# Laser_Centraal.net
KiCad netlist of a schematic drawn in EAGLE
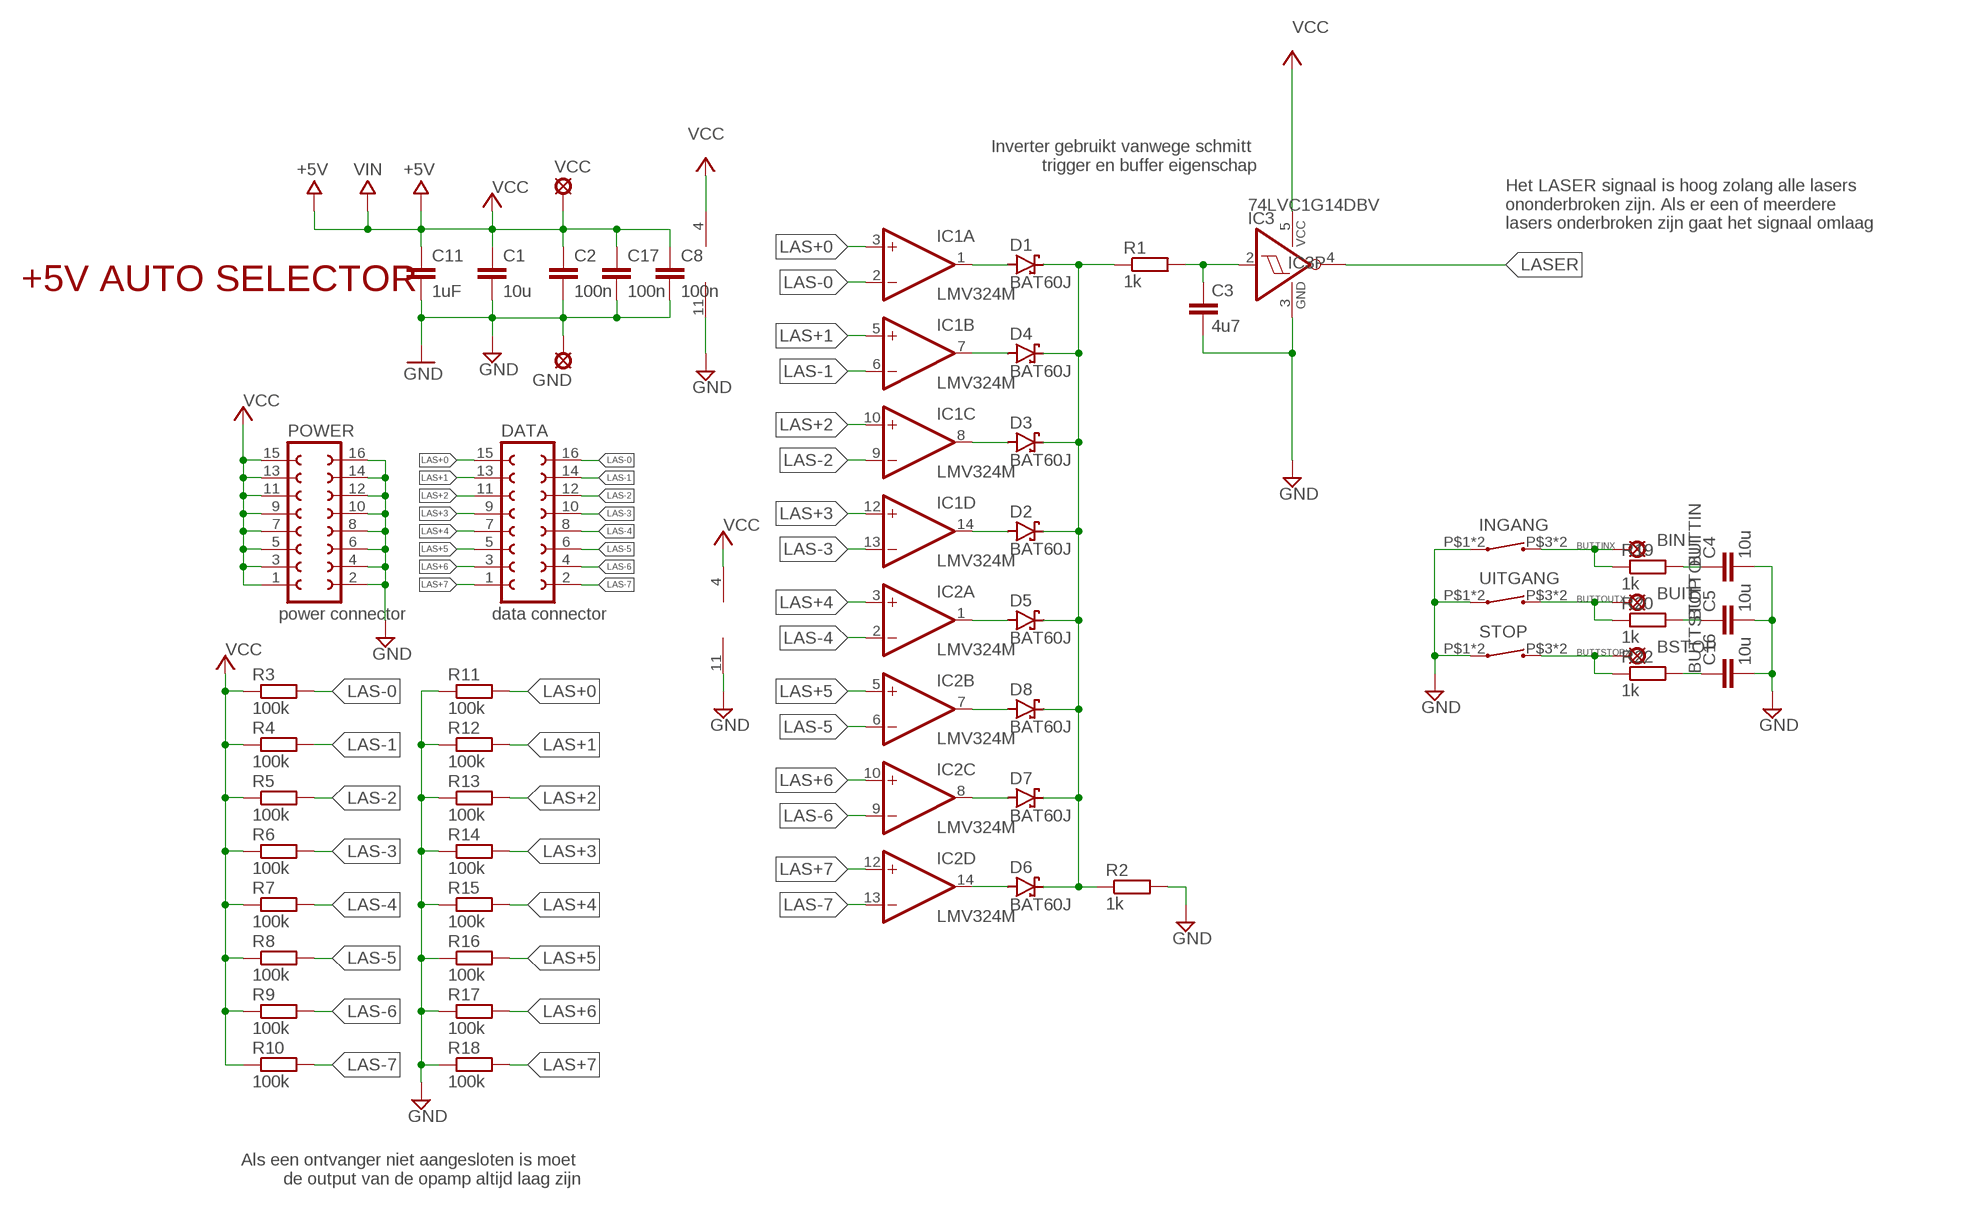
[diagram p0: schematic, sheet 1, part 1 of 2]
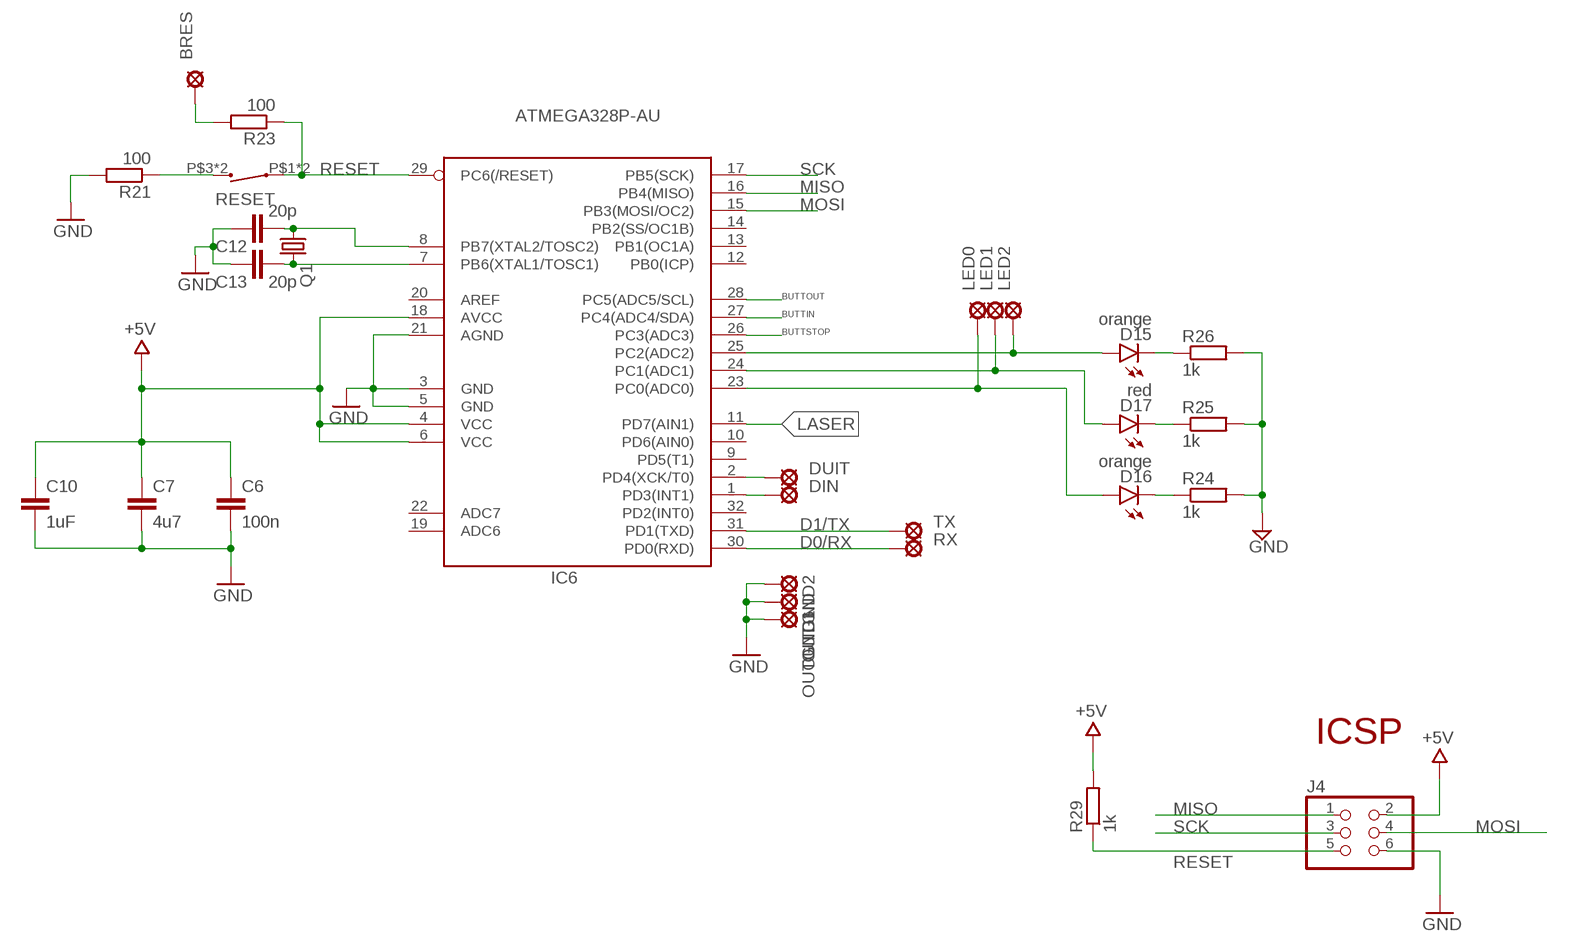
[diagram p1: schematic, sheet 1, part 2 of 2]

(export (version "E")
  (design (tool "Eeschema 10.0.6"))
  (components
    (comp (ref "BIN")
      (value "LSP10")
      (footprint "eagle-import:LSP10")
      (libsource (lib "eagle-import") (part "LSP10"))
    )
    (comp (ref "BRES")
      (value "LSP10")
      (footprint "eagle-import:LSP10")
      (libsource (lib "eagle-import") (part "LSP10"))
    )
    (comp (ref "BSTOP")
      (value "LSP10")
      (footprint "eagle-import:LSP10")
      (libsource (lib "eagle-import") (part "LSP10"))
    )
    (comp (ref "BUIT")
      (value "LSP10")
      (footprint "eagle-import:LSP10")
      (libsource (lib "eagle-import") (part "LSP10"))
    )
    (comp (ref "C1")
      (value "10u")
      (footprint "eagle-import:C0805")
      (libsource (lib "eagle-import") (part "C-EUC0805"))
    )
    (comp (ref "C2")
      (value "100n")
      (footprint "eagle-import:C0805")
      (libsource (lib "eagle-import") (part "C-EUC0805"))
    )
    (comp (ref "C3")
      (value "4u7")
      (footprint "eagle-import:C0805")
      (libsource (lib "eagle-import") (part "resistor_348_C-EUC0805"))
    )
    (comp (ref "C4")
      (value "10u")
      (footprint "eagle-import:C0805")
      (libsource (lib "eagle-import") (part "resistor_348_C-EUC0805"))
    )
    (comp (ref "C5")
      (value "10u")
      (footprint "eagle-import:C0805")
      (libsource (lib "eagle-import") (part "resistor_348_C-EUC0805"))
    )
    (comp (ref "C6")
      (value "100n")
      (footprint "eagle-import:C0805")
      (libsource (lib "eagle-import") (part "C-EUC0805"))
    )
    (comp (ref "C7")
      (value "4u7")
      (footprint "eagle-import:C0805")
      (libsource (lib "eagle-import") (part "C-EUC0805"))
    )
    (comp (ref "C8")
      (value "100n")
      (footprint "eagle-import:C0805")
      (libsource (lib "eagle-import") (part "C-EUC0805"))
    )
    (comp (ref "C10")
      (value "1uF")
      (footprint "eagle-import:C0805")
      (libsource (lib "eagle-import") (part "C-EUC0805"))
    )
    (comp (ref "C11")
      (value "1uF")
      (footprint "eagle-import:C0805")
      (libsource (lib "eagle-import") (part "C-EUC0805"))
    )
    (comp (ref "C12")
      (value "20p")
      (footprint "eagle-import:C0805")
      (libsource (lib "eagle-import") (part "C-EUC0805"))
    )
    (comp (ref "C13")
      (value "20p")
      (footprint "eagle-import:C0805")
      (libsource (lib "eagle-import") (part "C-EUC0805"))
    )
    (comp (ref "C16")
      (value "10u")
      (footprint "eagle-import:C0805")
      (libsource (lib "eagle-import") (part "resistor_348_C-EUC0805"))
    )
    (comp (ref "C17")
      (value "100n")
      (footprint "eagle-import:C0805")
      (libsource (lib "eagle-import") (part "C-EUC0805"))
    )
    (comp (ref "D1")
      (value "BAT60J")
      (footprint "eagle-import:SOD323_ST")
      (libsource (lib "eagle-import") (part "BAT60J"))
    )
    (comp (ref "D2")
      (value "BAT60J")
      (footprint "eagle-import:SOD323_ST")
      (libsource (lib "eagle-import") (part "BAT60J"))
    )
    (comp (ref "D3")
      (value "BAT60J")
      (footprint "eagle-import:SOD323_ST")
      (libsource (lib "eagle-import") (part "BAT60J"))
    )
    (comp (ref "D4")
      (value "BAT60J")
      (footprint "eagle-import:SOD323_ST")
      (libsource (lib "eagle-import") (part "BAT60J"))
    )
    (comp (ref "D5")
      (value "BAT60J")
      (footprint "eagle-import:SOD323_ST")
      (libsource (lib "eagle-import") (part "BAT60J"))
    )
    (comp (ref "D6")
      (value "BAT60J")
      (footprint "eagle-import:SOD323_ST")
      (libsource (lib "eagle-import") (part "BAT60J"))
    )
    (comp (ref "D7")
      (value "BAT60J")
      (footprint "eagle-import:SOD323_ST")
      (libsource (lib "eagle-import") (part "BAT60J"))
    )
    (comp (ref "D8")
      (value "BAT60J")
      (footprint "eagle-import:SOD323_ST")
      (libsource (lib "eagle-import") (part "BAT60J"))
    )
    (comp (ref "D15")
      (value "orange")
      (footprint "eagle-import:CHIP-LED0805")
      (libsource (lib "eagle-import") (part "LEDCHIP-LED0805"))
    )
    (comp (ref "D16")
      (value "orange")
      (footprint "eagle-import:CHIP-LED0805")
      (libsource (lib "eagle-import") (part "LEDCHIP-LED0805"))
    )
    (comp (ref "D17")
      (value "red")
      (footprint "eagle-import:CHIP-LED0805")
      (libsource (lib "eagle-import") (part "LEDCHIP-LED0805"))
    )
    (comp (ref "DATA")
      (value "FE08-2")
      (footprint "eagle-import:FE08-2")
      (libsource (lib "eagle-import") (part "FE08-2"))
    )
    (comp (ref "DIN")
      (value "LSP10")
      (footprint "eagle-import:LSP10")
      (libsource (lib "eagle-import") (part "LSP10"))
    )
    (comp (ref "DUIT")
      (value "LSP10")
      (footprint "eagle-import:LSP10")
      (libsource (lib "eagle-import") (part "LSP10"))
    )
    (comp (ref "GND")
      (value "LSP10")
      (footprint "eagle-import:LSP10")
      (libsource (lib "eagle-import") (part "LSP10"))
    )
    (comp (ref "IC1")
      (value "LMV324M")
      (footprint "eagle-import:SO14")
      (libsource (lib "eagle-import") (part "LMV324?M"))
    )
    (comp (ref "IC2")
      (value "LMV324M")
      (footprint "eagle-import:SO14")
      (libsource (lib "eagle-import") (part "LMV324?M"))
    )
    (comp (ref "IC3")
      (value "74LVC1G14DBV")
      (footprint "eagle-import:SOT23-5")
      (libsource (lib "eagle-import") (part "741G14DBVLVC"))
    )
    (comp (ref "IC6")
      (value "ATMEGA328P-AU")
      (footprint "eagle-import:TQFP32-08")
      (fields (field (name "MANUFACTURER") "ATMEL"))
      (libsource (lib "eagle-import") (part "ATMEGA328P-32AU"))
    )
    (comp (ref "INGANG")
      (value "BRIGHTTSA061G100-250_SWITCH")
      (footprint "eagle-import:BRIGHTTSA061G100-250")
      (libsource (lib "eagle-import") (part "BRIGHTTSA061G100-250_SWITCH"))
    )
    (comp (ref "J4")
      (value "0114_PH254-203DF118A00V")
      (footprint "eagle-import:2X03")
      (fields (field (name "PART_NUMBER") "PH254-203DF118A00V"))
      (libsource (lib "eagle-import") (part "0114_PH254-203DF118A00V"))
    )
    (comp (ref "LED0")
      (value "LSP10")
      (footprint "eagle-import:LSP10")
      (libsource (lib "eagle-import") (part "LSP10"))
    )
    (comp (ref "LED1")
      (value "LSP10")
      (footprint "eagle-import:LSP10")
      (libsource (lib "eagle-import") (part "LSP10"))
    )
    (comp (ref "LED2")
      (value "LSP10")
      (footprint "eagle-import:LSP10")
      (libsource (lib "eagle-import") (part "LSP10"))
    )
    (comp (ref "OUTGND")
      (value "LSP10")
      (footprint "eagle-import:LSP10")
      (libsource (lib "eagle-import") (part "LSP10"))
    )
    (comp (ref "OUTGND1")
      (value "LSP10")
      (footprint "eagle-import:LSP10")
      (libsource (lib "eagle-import") (part "LSP10"))
    )
    (comp (ref "OUTGND2")
      (value "LSP10")
      (footprint "eagle-import:LSP10")
      (libsource (lib "eagle-import") (part "LSP10"))
    )
    (comp (ref "POWER")
      (value "FE08-2")
      (footprint "eagle-import:FE08-2")
      (fields (field (name "SPICEPREFIX") "X"))
      (libsource (lib "eagle-import") (part "FE08-2"))
    )
    (comp (ref "Q1")
      (value "CRYSTALHC49U70")
      (footprint "eagle-import:HC49U70")
      (libsource (lib "eagle-import") (part "CRYSTALHC49U70"))
    )
    (comp (ref "R1")
      (value "1k")
      (footprint "eagle-import:R0805")
      (libsource (lib "eagle-import") (part "R-EU_R0805"))
    )
    (comp (ref "R2")
      (value "1k")
      (footprint "eagle-import:R0805")
      (libsource (lib "eagle-import") (part "R-EU_R0805"))
    )
    (comp (ref "R3")
      (value "100k")
      (footprint "eagle-import:R0805")
      (libsource (lib "eagle-import") (part "R-EU_R0805"))
    )
    (comp (ref "R4")
      (value "100k")
      (footprint "eagle-import:R0805")
      (libsource (lib "eagle-import") (part "R-EU_R0805"))
    )
    (comp (ref "R5")
      (value "100k")
      (footprint "eagle-import:R0805")
      (libsource (lib "eagle-import") (part "R-EU_R0805"))
    )
    (comp (ref "R6")
      (value "100k")
      (footprint "eagle-import:R0805")
      (libsource (lib "eagle-import") (part "R-EU_R0805"))
    )
    (comp (ref "R7")
      (value "100k")
      (footprint "eagle-import:R0805")
      (libsource (lib "eagle-import") (part "R-EU_R0805"))
    )
    (comp (ref "R8")
      (value "100k")
      (footprint "eagle-import:R0805")
      (libsource (lib "eagle-import") (part "R-EU_R0805"))
    )
    (comp (ref "R9")
      (value "100k")
      (footprint "eagle-import:R0805")
      (libsource (lib "eagle-import") (part "R-EU_R0805"))
    )
    (comp (ref "R10")
      (value "100k")
      (footprint "eagle-import:R0805")
      (libsource (lib "eagle-import") (part "R-EU_R0805"))
    )
    (comp (ref "R11")
      (value "100k")
      (footprint "eagle-import:R0805")
      (libsource (lib "eagle-import") (part "R-EU_R0805"))
    )
    (comp (ref "R12")
      (value "100k")
      (footprint "eagle-import:R0805")
      (libsource (lib "eagle-import") (part "R-EU_R0805"))
    )
    (comp (ref "R13")
      (value "100k")
      (footprint "eagle-import:R0805")
      (libsource (lib "eagle-import") (part "R-EU_R0805"))
    )
    (comp (ref "R14")
      (value "100k")
      (footprint "eagle-import:R0805")
      (libsource (lib "eagle-import") (part "R-EU_R0805"))
    )
    (comp (ref "R15")
      (value "100k")
      (footprint "eagle-import:R0805")
      (libsource (lib "eagle-import") (part "R-EU_R0805"))
    )
    (comp (ref "R16")
      (value "100k")
      (footprint "eagle-import:R0805")
      (libsource (lib "eagle-import") (part "R-EU_R0805"))
    )
    (comp (ref "R17")
      (value "100k")
      (footprint "eagle-import:R0805")
      (libsource (lib "eagle-import") (part "R-EU_R0805"))
    )
    (comp (ref "R18")
      (value "100k")
      (footprint "eagle-import:R0805")
      (libsource (lib "eagle-import") (part "R-EU_R0805"))
    )
    (comp (ref "R19")
      (value "1k")
      (footprint "eagle-import:R0805")
      (libsource (lib "eagle-import") (part "R-EU_R0805"))
    )
    (comp (ref "R20")
      (value "1k")
      (footprint "eagle-import:R0805")
      (libsource (lib "eagle-import") (part "R-EU_R0805"))
    )
    (comp (ref "R21")
      (value "100")
      (footprint "eagle-import:R0805")
      (libsource (lib "eagle-import") (part "R-EU_R0805"))
    )
    (comp (ref "R22")
      (value "1k")
      (footprint "eagle-import:R0805")
      (libsource (lib "eagle-import") (part "R-EU_R0805"))
    )
    (comp (ref "R23")
      (value "100")
      (footprint "eagle-import:R0805")
      (libsource (lib "eagle-import") (part "R-EU_R0805"))
    )
    (comp (ref "R24")
      (value "1k")
      (footprint "eagle-import:R0805")
      (libsource (lib "eagle-import") (part "R-EU_R0805"))
    )
    (comp (ref "R25")
      (value "1k")
      (footprint "eagle-import:R0805")
      (libsource (lib "eagle-import") (part "R-EU_R0805"))
    )
    (comp (ref "R26")
      (value "1k")
      (footprint "eagle-import:R0805")
      (libsource (lib "eagle-import") (part "R-EU_R0805"))
    )
    (comp (ref "R29")
      (value "1k")
      (footprint "eagle-import:R0805")
      (libsource (lib "eagle-import") (part "R-EU_R0805"))
    )
    (comp (ref "RESET")
      (value "BRIGHTTSA061G100-250_SWITCH")
      (footprint "eagle-import:BRIGHTTSA061G100-250")
      (libsource (lib "eagle-import") (part "BRIGHTTSA061G100-250_SWITCH"))
    )
    (comp (ref "RX")
      (value "LSP10")
      (footprint "eagle-import:LSP10")
      (libsource (lib "eagle-import") (part "LSP10"))
    )
    (comp (ref "STOP")
      (value "BRIGHTTSA061G100-250_SWITCH")
      (footprint "eagle-import:BRIGHTTSA061G100-250")
      (libsource (lib "eagle-import") (part "BRIGHTTSA061G100-250_SWITCH"))
    )
    (comp (ref "TX")
      (value "LSP10")
      (footprint "eagle-import:LSP10")
      (libsource (lib "eagle-import") (part "LSP10"))
    )
    (comp (ref "UITGANG")
      (value "BRIGHTTSA061G100-250_SWITCH")
      (footprint "eagle-import:BRIGHTTSA061G100-250")
      (libsource (lib "eagle-import") (part "BRIGHTTSA061G100-250_SWITCH"))
    )
    (comp (ref "VCC")
      (value "LSP10")
      (footprint "eagle-import:LSP10")
      (libsource (lib "eagle-import") (part "LSP10"))
    )
  )
  (nets
    (net (code "1") (name "+5V") (class "Default")
      (node (ref "C1") (pin "1") (pinfunction "1_1") (pintype "passive"))
      (node (ref "C10") (pin "1") (pinfunction "1_1") (pintype "passive"))
      (node (ref "C11") (pin "1") (pinfunction "1_1") (pintype "passive"))
      (node (ref "C17") (pin "1") (pinfunction "1_1") (pintype "passive"))
      (node (ref "C2") (pin "1") (pinfunction "1_1") (pintype "passive"))
      (node (ref "C6") (pin "1") (pinfunction "1_1") (pintype "passive"))
      (node (ref "C7") (pin "1") (pinfunction "1_1") (pintype "passive"))
      (node (ref "C8") (pin "1") (pinfunction "1_1") (pintype "passive"))
      (node (ref "IC1") (pin "4") (pinfunction "V+_4") (pintype "power_in"))
      (node (ref "IC2") (pin "4") (pinfunction "V+_4") (pintype "power_in"))
      (node (ref "IC3") (pin "5") (pinfunction "VCC_5") (pintype "power_in"))
      (node (ref "IC6") (pin "18") (pinfunction "AVCC_18") (pintype "bidirectional"))
      (node (ref "IC6") (pin "4") (pinfunction "VCC_4") (pintype "bidirectional"))
      (node (ref "IC6") (pin "6") (pinfunction "VCC_6") (pintype "bidirectional"))
      (node (ref "J4") (pin "2") (pinfunction "2_2") (pintype "passive"))
      (node (ref "POWER") (pin "1") (pinfunction "1_1") (pintype "passive"))
      (node (ref "POWER") (pin "11") (pinfunction "11_11") (pintype "passive"))
      (node (ref "POWER") (pin "13") (pinfunction "13_13") (pintype "passive"))
      (node (ref "POWER") (pin "15") (pinfunction "15_15") (pintype "passive"))
      (node (ref "POWER") (pin "3") (pinfunction "3_3") (pintype "passive"))
      (node (ref "POWER") (pin "5") (pinfunction "5_5") (pintype "passive"))
      (node (ref "POWER") (pin "7") (pinfunction "7_7") (pintype "passive"))
      (node (ref "POWER") (pin "9") (pinfunction "9_9") (pintype "passive"))
      (node (ref "R10") (pin "1") (pinfunction "1_1") (pintype "passive"))
      (node (ref "R29") (pin "2") (pinfunction "2_2") (pintype "passive"))
      (node (ref "R3") (pin "1") (pinfunction "1_1") (pintype "passive"))
      (node (ref "R4") (pin "1") (pinfunction "1_1") (pintype "passive"))
      (node (ref "R5") (pin "1") (pinfunction "1_1") (pintype "passive"))
      (node (ref "R6") (pin "1") (pinfunction "1_1") (pintype "passive"))
      (node (ref "R7") (pin "1") (pinfunction "1_1") (pintype "passive"))
      (node (ref "R8") (pin "1") (pinfunction "1_1") (pintype "passive"))
      (node (ref "R9") (pin "1") (pinfunction "1_1") (pintype "passive"))
      (node (ref "VCC") (pin "MP") (pinfunction "MP_MP") (pintype "passive"))
    )
    (net (code "2") (name "/BUTTIN") (class "Default")
      (node (ref "C4") (pin "1") (pinfunction "1_1") (pintype "passive"))
      (node (ref "IC6") (pin "27") (pinfunction "PC4(ADC4/SDA)_27") (pintype "bidirectional"))
      (node (ref "R19") (pin "2") (pinfunction "2_2") (pintype "passive"))
    )
    (net (code "3") (name "/BUTTINX") (class "Default")
      (node (ref "BIN") (pin "MP") (pinfunction "MP_MP") (pintype "passive"))
      (node (ref "INGANG") (pin "P$3") (pinfunction "2_P$3") (pintype "passive"))
      (node (ref "INGANG") (pin "P$4") (pinfunction "2_P$4") (pintype "passive"))
      (node (ref "R19") (pin "1") (pinfunction "1_1") (pintype "passive"))
    )
    (net (code "4") (name "/BUTTOUT") (class "Default")
      (node (ref "C5") (pin "1") (pinfunction "1_1") (pintype "passive"))
      (node (ref "IC6") (pin "28") (pinfunction "PC5(ADC5/SCL)_28") (pintype "bidirectional"))
      (node (ref "R20") (pin "2") (pinfunction "2_2") (pintype "passive"))
    )
    (net (code "5") (name "/BUTTOUTX") (class "Default")
      (node (ref "BUIT") (pin "MP") (pinfunction "MP_MP") (pintype "passive"))
      (node (ref "R20") (pin "1") (pinfunction "1_1") (pintype "passive"))
      (node (ref "UITGANG") (pin "P$3") (pinfunction "2_P$3") (pintype "passive"))
      (node (ref "UITGANG") (pin "P$4") (pinfunction "2_P$4") (pintype "passive"))
    )
    (net (code "6") (name "/BUTTSTOP") (class "Default")
      (node (ref "C16") (pin "1") (pinfunction "1_1") (pintype "passive"))
      (node (ref "IC6") (pin "26") (pinfunction "PC3(ADC3)_26") (pintype "bidirectional"))
      (node (ref "R22") (pin "2") (pinfunction "2_2") (pintype "passive"))
    )
    (net (code "7") (name "/BUTTSTOPX") (class "Default")
      (node (ref "BSTOP") (pin "MP") (pinfunction "MP_MP") (pintype "passive"))
      (node (ref "R22") (pin "1") (pinfunction "1_1") (pintype "passive"))
      (node (ref "STOP") (pin "P$3") (pinfunction "2_P$3") (pintype "passive"))
      (node (ref "STOP") (pin "P$4") (pinfunction "2_P$4") (pintype "passive"))
    )
    (net (code "8") (name "/D0{slash}RX") (class "Default")
      (node (ref "IC6") (pin "30") (pinfunction "PD0(RXD)_30") (pintype "bidirectional"))
      (node (ref "RX") (pin "MP") (pinfunction "MP_MP") (pintype "passive"))
    )
    (net (code "9") (name "/D1{slash}TX") (class "Default")
      (node (ref "IC6") (pin "31") (pinfunction "PD1(TXD)_31") (pintype "bidirectional"))
      (node (ref "TX") (pin "MP") (pinfunction "MP_MP") (pintype "passive"))
    )
    (net (code "10") (name "/MISO") (class "Default")
      (node (ref "IC6") (pin "16") (pinfunction "PB4(MISO)_16") (pintype "bidirectional"))
      (node (ref "J4") (pin "1") (pinfunction "1_1") (pintype "passive"))
    )
    (net (code "11") (name "/MOSI") (class "Default")
      (node (ref "IC6") (pin "15") (pinfunction "PB3(MOSI/OC2)_15") (pintype "bidirectional"))
      (node (ref "J4") (pin "4") (pinfunction "4_4") (pintype "passive"))
    )
    (net (code "12") (name "/RESET") (class "Default")
      (node (ref "IC6") (pin "29") (pinfunction "PC6(/RESET)_29") (pintype "bidirectional"))
      (node (ref "J4") (pin "5") (pinfunction "5_5") (pintype "passive"))
      (node (ref "R23") (pin "1") (pinfunction "1_1") (pintype "passive"))
      (node (ref "R29") (pin "1") (pinfunction "1_1") (pintype "passive"))
      (node (ref "RESET") (pin "P$1") (pinfunction "1_P$1") (pintype "passive"))
      (node (ref "RESET") (pin "P$2") (pinfunction "1_P$2") (pintype "passive"))
    )
    (net (code "13") (name "/SCK") (class "Default")
      (node (ref "IC6") (pin "17") (pinfunction "PB5(SCK)_17") (pintype "bidirectional"))
      (node (ref "J4") (pin "3") (pinfunction "3_3") (pintype "passive"))
    )
    (net (code "14") (name "GND") (class "Default")
      (node (ref "C1") (pin "2") (pinfunction "2_2") (pintype "passive"))
      (node (ref "C10") (pin "2") (pinfunction "2_2") (pintype "passive"))
      (node (ref "C11") (pin "2") (pinfunction "2_2") (pintype "passive"))
      (node (ref "C12") (pin "1") (pinfunction "1_1") (pintype "passive"))
      (node (ref "C13") (pin "1") (pinfunction "1_1") (pintype "passive"))
      (node (ref "C16") (pin "2") (pinfunction "2_2") (pintype "passive"))
      (node (ref "C17") (pin "2") (pinfunction "2_2") (pintype "passive"))
      (node (ref "C2") (pin "2") (pinfunction "2_2") (pintype "passive"))
      (node (ref "C3") (pin "2") (pinfunction "2_2") (pintype "passive"))
      (node (ref "C4") (pin "2") (pinfunction "2_2") (pintype "passive"))
      (node (ref "C5") (pin "2") (pinfunction "2_2") (pintype "passive"))
      (node (ref "C6") (pin "2") (pinfunction "2_2") (pintype "passive"))
      (node (ref "C7") (pin "2") (pinfunction "2_2") (pintype "passive"))
      (node (ref "C8") (pin "2") (pinfunction "2_2") (pintype "passive"))
      (node (ref "GND") (pin "MP") (pinfunction "MP_MP") (pintype "passive"))
      (node (ref "IC1") (pin "11") (pinfunction "V-_11") (pintype "power_in"))
      (node (ref "IC2") (pin "11") (pinfunction "V-_11") (pintype "power_in"))
      (node (ref "IC3") (pin "3") (pinfunction "GND_3") (pintype "power_in"))
      (node (ref "IC6") (pin "21") (pinfunction "AGND_21") (pintype "bidirectional"))
      (node (ref "IC6") (pin "3") (pinfunction "GND_3") (pintype "bidirectional"))
      (node (ref "IC6") (pin "5") (pinfunction "GND_5") (pintype "bidirectional"))
      (node (ref "INGANG") (pin "P$1") (pinfunction "1_P$1") (pintype "passive"))
      (node (ref "INGANG") (pin "P$2") (pinfunction "1_P$2") (pintype "passive"))
      (node (ref "J4") (pin "6") (pinfunction "6_6") (pintype "passive"))
      (node (ref "OUTGND") (pin "MP") (pinfunction "MP_MP") (pintype "passive"))
      (node (ref "OUTGND1") (pin "MP") (pinfunction "MP_MP") (pintype "passive"))
      (node (ref "OUTGND2") (pin "MP") (pinfunction "MP_MP") (pintype "passive"))
      (node (ref "POWER") (pin "10") (pinfunction "10_10") (pintype "passive"))
      (node (ref "POWER") (pin "12") (pinfunction "12_12") (pintype "passive"))
      (node (ref "POWER") (pin "14") (pinfunction "14_14") (pintype "passive"))
      (node (ref "POWER") (pin "16") (pinfunction "16_16") (pintype "passive"))
      (node (ref "POWER") (pin "2") (pinfunction "2_2") (pintype "passive"))
      (node (ref "POWER") (pin "4") (pinfunction "4_4") (pintype "passive"))
      (node (ref "POWER") (pin "6") (pinfunction "6_6") (pintype "passive"))
      (node (ref "POWER") (pin "8") (pinfunction "8_8") (pintype "passive"))
      (node (ref "R11") (pin "1") (pinfunction "1_1") (pintype "passive"))
      (node (ref "R12") (pin "1") (pinfunction "1_1") (pintype "passive"))
      (node (ref "R13") (pin "1") (pinfunction "1_1") (pintype "passive"))
      (node (ref "R14") (pin "1") (pinfunction "1_1") (pintype "passive"))
      (node (ref "R15") (pin "1") (pinfunction "1_1") (pintype "passive"))
      (node (ref "R16") (pin "1") (pinfunction "1_1") (pintype "passive"))
      (node (ref "R17") (pin "1") (pinfunction "1_1") (pintype "passive"))
      (node (ref "R18") (pin "1") (pinfunction "1_1") (pintype "passive"))
      (node (ref "R2") (pin "2") (pinfunction "2_2") (pintype "passive"))
      (node (ref "R21") (pin "2") (pinfunction "2_2") (pintype "passive"))
      (node (ref "R24") (pin "2") (pinfunction "2_2") (pintype "passive"))
      (node (ref "R25") (pin "2") (pinfunction "2_2") (pintype "passive"))
      (node (ref "R26") (pin "2") (pinfunction "2_2") (pintype "passive"))
      (node (ref "STOP") (pin "P$1") (pinfunction "1_P$1") (pintype "passive"))
      (node (ref "STOP") (pin "P$2") (pinfunction "1_P$2") (pintype "passive"))
      (node (ref "UITGANG") (pin "P$1") (pinfunction "1_P$1") (pintype "passive"))
      (node (ref "UITGANG") (pin "P$2") (pinfunction "1_P$2") (pintype "passive"))
    )
    (net (code "15") (name "LAS+0") (class "Default")
      (node (ref "DATA") (pin "15") (pinfunction "15_15") (pintype "passive"))
      (node (ref "IC1") (pin "3") (pinfunction "+IN_3") (pintype "input"))
      (node (ref "R11") (pin "2") (pinfunction "2_2") (pintype "passive"))
    )
    (net (code "16") (name "LAS+1") (class "Default")
      (node (ref "DATA") (pin "13") (pinfunction "13_13") (pintype "passive"))
      (node (ref "IC1") (pin "5") (pinfunction "+IN_5") (pintype "input"))
      (node (ref "R12") (pin "2") (pinfunction "2_2") (pintype "passive"))
    )
    (net (code "17") (name "LAS+2") (class "Default")
      (node (ref "DATA") (pin "11") (pinfunction "11_11") (pintype "passive"))
      (node (ref "IC1") (pin "10") (pinfunction "+IN_10") (pintype "input"))
      (node (ref "R13") (pin "2") (pinfunction "2_2") (pintype "passive"))
    )
    (net (code "18") (name "LAS+3") (class "Default")
      (node (ref "DATA") (pin "9") (pinfunction "9_9") (pintype "passive"))
      (node (ref "IC1") (pin "12") (pinfunction "+IN_12") (pintype "input"))
      (node (ref "R14") (pin "2") (pinfunction "2_2") (pintype "passive"))
    )
    (net (code "19") (name "LAS+4") (class "Default")
      (node (ref "DATA") (pin "7") (pinfunction "7_7") (pintype "passive"))
      (node (ref "IC2") (pin "3") (pinfunction "+IN_3") (pintype "input"))
      (node (ref "R15") (pin "2") (pinfunction "2_2") (pintype "passive"))
    )
    (net (code "20") (name "LAS+5") (class "Default")
      (node (ref "DATA") (pin "5") (pinfunction "5_5") (pintype "passive"))
      (node (ref "IC2") (pin "5") (pinfunction "+IN_5") (pintype "input"))
      (node (ref "R16") (pin "2") (pinfunction "2_2") (pintype "passive"))
    )
    (net (code "21") (name "LAS+6") (class "Default")
      (node (ref "DATA") (pin "3") (pinfunction "3_3") (pintype "passive"))
      (node (ref "IC2") (pin "10") (pinfunction "+IN_10") (pintype "input"))
      (node (ref "R17") (pin "2") (pinfunction "2_2") (pintype "passive"))
    )
    (net (code "22") (name "LAS+7") (class "Default")
      (node (ref "DATA") (pin "1") (pinfunction "1_1") (pintype "passive"))
      (node (ref "IC2") (pin "12") (pinfunction "+IN_12") (pintype "input"))
      (node (ref "R18") (pin "2") (pinfunction "2_2") (pintype "passive"))
    )
    (net (code "23") (name "LAS-0") (class "Default")
      (node (ref "DATA") (pin "16") (pinfunction "16_16") (pintype "passive"))
      (node (ref "IC1") (pin "2") (pinfunction "-IN_2") (pintype "input"))
      (node (ref "R3") (pin "2") (pinfunction "2_2") (pintype "passive"))
    )
    (net (code "24") (name "LAS-1") (class "Default")
      (node (ref "DATA") (pin "14") (pinfunction "14_14") (pintype "passive"))
      (node (ref "IC1") (pin "6") (pinfunction "-IN_6") (pintype "input"))
      (node (ref "R4") (pin "2") (pinfunction "2_2") (pintype "passive"))
    )
    (net (code "25") (name "LAS-2") (class "Default")
      (node (ref "DATA") (pin "12") (pinfunction "12_12") (pintype "passive"))
      (node (ref "IC1") (pin "9") (pinfunction "-IN_9") (pintype "input"))
      (node (ref "R5") (pin "2") (pinfunction "2_2") (pintype "passive"))
    )
    (net (code "26") (name "LAS-3") (class "Default")
      (node (ref "DATA") (pin "10") (pinfunction "10_10") (pintype "passive"))
      (node (ref "IC1") (pin "13") (pinfunction "-IN_13") (pintype "input"))
      (node (ref "R6") (pin "2") (pinfunction "2_2") (pintype "passive"))
    )
    (net (code "27") (name "LAS-4") (class "Default")
      (node (ref "DATA") (pin "8") (pinfunction "8_8") (pintype "passive"))
      (node (ref "IC2") (pin "2") (pinfunction "-IN_2") (pintype "input"))
      (node (ref "R7") (pin "2") (pinfunction "2_2") (pintype "passive"))
    )
    (net (code "28") (name "LAS-5") (class "Default")
      (node (ref "DATA") (pin "6") (pinfunction "6_6") (pintype "passive"))
      (node (ref "IC2") (pin "6") (pinfunction "-IN_6") (pintype "input"))
      (node (ref "R8") (pin "2") (pinfunction "2_2") (pintype "passive"))
    )
    (net (code "29") (name "LAS-6") (class "Default")
      (node (ref "DATA") (pin "4") (pinfunction "4_4") (pintype "passive"))
      (node (ref "IC2") (pin "9") (pinfunction "-IN_9") (pintype "input"))
      (node (ref "R9") (pin "2") (pinfunction "2_2") (pintype "passive"))
    )
    (net (code "30") (name "LAS-7") (class "Default")
      (node (ref "DATA") (pin "2") (pinfunction "2_2") (pintype "passive"))
      (node (ref "IC2") (pin "13") (pinfunction "-IN_13") (pintype "input"))
      (node (ref "R10") (pin "2") (pinfunction "2_2") (pintype "passive"))
    )
    (net (code "31") (name "LASER") (class "Default")
      (node (ref "IC3") (pin "4") (pinfunction "O_4") (pintype "output"))
      (node (ref "IC6") (pin "11") (pinfunction "PD7(AIN1)_11") (pintype "bidirectional"))
    )
    (net (code "32") (name "Net-(BRES-PadMP)") (class "Default")
      (node (ref "BRES") (pin "MP") (pinfunction "MP_MP") (pintype "passive"))
      (node (ref "R23") (pin "2") (pinfunction "2_2") (pintype "passive"))
    )
    (net (code "33") (name "Net-(D1-PadC)") (class "Default")
      (node (ref "D1") (pin "C") (pinfunction "C_C") (pintype "passive"))
      (node (ref "D2") (pin "C") (pinfunction "C_C") (pintype "passive"))
      (node (ref "D3") (pin "C") (pinfunction "C_C") (pintype "passive"))
      (node (ref "D4") (pin "C") (pinfunction "C_C") (pintype "passive"))
      (node (ref "D5") (pin "C") (pinfunction "C_C") (pintype "passive"))
      (node (ref "D6") (pin "C") (pinfunction "C_C") (pintype "passive"))
      (node (ref "D7") (pin "C") (pinfunction "C_C") (pintype "passive"))
      (node (ref "D8") (pin "C") (pinfunction "C_C") (pintype "passive"))
      (node (ref "R1") (pin "1") (pinfunction "1_1") (pintype "passive"))
      (node (ref "R2") (pin "1") (pinfunction "1_1") (pintype "passive"))
    )
    (net (code "34") (name "Net-(D15-PadC)") (class "Default")
      (node (ref "D15") (pin "C") (pinfunction "C_C") (pintype "passive"))
      (node (ref "R26") (pin "1") (pinfunction "1_1") (pintype "passive"))
    )
    (net (code "35") (name "Net-(D16-PadC)") (class "Default")
      (node (ref "D16") (pin "C") (pinfunction "C_C") (pintype "passive"))
      (node (ref "R24") (pin "1") (pinfunction "1_1") (pintype "passive"))
    )
    (net (code "36") (name "Net-(D17-PadC)") (class "Default")
      (node (ref "D17") (pin "C") (pinfunction "C_C") (pintype "passive"))
      (node (ref "R25") (pin "1") (pinfunction "1_1") (pintype "passive"))
    )
    (net (code "37") (name "Net-(IC1A-OUT)") (class "Default")
      (node (ref "D1") (pin "A") (pinfunction "A_A") (pintype "passive"))
      (node (ref "IC1") (pin "1") (pinfunction "OUT_1") (pintype "output"))
    )
    (net (code "38") (name "Net-(IC1B-OUT)") (class "Default")
      (node (ref "D4") (pin "A") (pinfunction "A_A") (pintype "passive"))
      (node (ref "IC1") (pin "7") (pinfunction "OUT_7") (pintype "output"))
    )
    (net (code "39") (name "Net-(IC1C-OUT)") (class "Default")
      (node (ref "D3") (pin "A") (pinfunction "A_A") (pintype "passive"))
      (node (ref "IC1") (pin "8") (pinfunction "OUT_8") (pintype "output"))
    )
    (net (code "40") (name "Net-(IC1D-OUT)") (class "Default")
      (node (ref "D2") (pin "A") (pinfunction "A_A") (pintype "passive"))
      (node (ref "IC1") (pin "14") (pinfunction "OUT_14") (pintype "output"))
    )
    (net (code "41") (name "Net-(IC2A-OUT)") (class "Default")
      (node (ref "D5") (pin "A") (pinfunction "A_A") (pintype "passive"))
      (node (ref "IC2") (pin "1") (pinfunction "OUT_1") (pintype "output"))
    )
    (net (code "42") (name "Net-(IC2B-OUT)") (class "Default")
      (node (ref "D8") (pin "A") (pinfunction "A_A") (pintype "passive"))
      (node (ref "IC2") (pin "7") (pinfunction "OUT_7") (pintype "output"))
    )
    (net (code "43") (name "Net-(IC2C-OUT)") (class "Default")
      (node (ref "D7") (pin "A") (pinfunction "A_A") (pintype "passive"))
      (node (ref "IC2") (pin "8") (pinfunction "OUT_8") (pintype "output"))
    )
    (net (code "44") (name "Net-(IC2D-OUT)") (class "Default")
      (node (ref "D6") (pin "A") (pinfunction "A_A") (pintype "passive"))
      (node (ref "IC2") (pin "14") (pinfunction "OUT_14") (pintype "output"))
    )
    (net (code "45") (name "Net-(IC3A-I)") (class "Default")
      (node (ref "C3") (pin "1") (pinfunction "1_1") (pintype "passive"))
      (node (ref "IC3") (pin "2") (pinfunction "I_2") (pintype "input"))
      (node (ref "R1") (pin "2") (pinfunction "2_2") (pintype "passive"))
    )
    (net (code "46") (name "Net-(IC6-PB6(XTAL1{slash}TOSC1))") (class "Default")
      (node (ref "C13") (pin "2") (pinfunction "2_2") (pintype "passive"))
      (node (ref "IC6") (pin "7") (pinfunction "PB6(XTAL1/TOSC1)_7") (pintype "bidirectional"))
      (node (ref "Q1") (pin "2") (pinfunction "2_2") (pintype "passive"))
    )
    (net (code "47") (name "Net-(IC6-PB7(XTAL2{slash}TOSC2))") (class "Default")
      (node (ref "C12") (pin "2") (pinfunction "2_2") (pintype "passive"))
      (node (ref "IC6") (pin "8") (pinfunction "PB7(XTAL2/TOSC2)_8") (pintype "bidirectional"))
      (node (ref "Q1") (pin "1") (pinfunction "1_1") (pintype "passive"))
    )
    (net (code "48") (name "Net-(IC6-PC0(ADC0))") (class "Default")
      (node (ref "D16") (pin "A") (pinfunction "A_A") (pintype "passive"))
      (node (ref "IC6") (pin "23") (pinfunction "PC0(ADC0)_23") (pintype "bidirectional"))
      (node (ref "LED0") (pin "MP") (pinfunction "MP_MP") (pintype "passive"))
    )
    (net (code "49") (name "Net-(IC6-PC1(ADC1))") (class "Default")
      (node (ref "D17") (pin "A") (pinfunction "A_A") (pintype "passive"))
      (node (ref "IC6") (pin "24") (pinfunction "PC1(ADC1)_24") (pintype "bidirectional"))
      (node (ref "LED1") (pin "MP") (pinfunction "MP_MP") (pintype "passive"))
    )
    (net (code "50") (name "Net-(IC6-PC2(ADC2))") (class "Default")
      (node (ref "D15") (pin "A") (pinfunction "A_A") (pintype "passive"))
      (node (ref "IC6") (pin "25") (pinfunction "PC2(ADC2)_25") (pintype "bidirectional"))
      (node (ref "LED2") (pin "MP") (pinfunction "MP_MP") (pintype "passive"))
    )
    (net (code "51") (name "Net-(IC6-PD3(INT1))") (class "Default")
      (node (ref "DIN") (pin "MP") (pinfunction "MP_MP") (pintype "passive"))
      (node (ref "IC6") (pin "1") (pinfunction "PD3(INT1)_1") (pintype "bidirectional"))
    )
    (net (code "52") (name "Net-(IC6-PD4(XCK{slash}T0))") (class "Default")
      (node (ref "DUIT") (pin "MP") (pinfunction "MP_MP") (pintype "passive"))
      (node (ref "IC6") (pin "2") (pinfunction "PD4(XCK/T0)_2") (pintype "bidirectional"))
    )
    (net (code "53") (name "Net-(R21-Pad1)") (class "Default")
      (node (ref "R21") (pin "1") (pinfunction "1_1") (pintype "passive"))
      (node (ref "RESET") (pin "P$3") (pinfunction "2_P$3") (pintype "passive"))
      (node (ref "RESET") (pin "P$4") (pinfunction "2_P$4") (pintype "passive"))
    )
    (net (code "54") (name "unconnected-(IC6-ADC6-Pad19)") (class "Default")
      (node (ref "IC6") (pin "19") (pinfunction "ADC6_19") (pintype "bidirectional"))
    )
    (net (code "55") (name "unconnected-(IC6-ADC7-Pad22)") (class "Default")
      (node (ref "IC6") (pin "22") (pinfunction "ADC7_22") (pintype "bidirectional"))
    )
    (net (code "56") (name "unconnected-(IC6-AREF-Pad20)") (class "Default")
      (node (ref "IC6") (pin "20") (pinfunction "AREF_20") (pintype "bidirectional"))
    )
    (net (code "57") (name "unconnected-(IC6-PB0(ICP)-Pad12)") (class "Default")
      (node (ref "IC6") (pin "12") (pinfunction "PB0(ICP)_12") (pintype "bidirectional"))
    )
    (net (code "58") (name "unconnected-(IC6-PB1(OC1A)-Pad13)") (class "Default")
      (node (ref "IC6") (pin "13") (pinfunction "PB1(OC1A)_13") (pintype "bidirectional"))
    )
    (net (code "59") (name "unconnected-(IC6-PB2(SS{slash}OC1B)-Pad14)") (class "Default")
      (node (ref "IC6") (pin "14") (pinfunction "PB2(SS/OC1B)_14") (pintype "bidirectional"))
    )
    (net (code "60") (name "unconnected-(IC6-PD2(INT0)-Pad32)") (class "Default")
      (node (ref "IC6") (pin "32") (pinfunction "PD2(INT0)_32") (pintype "bidirectional"))
    )
    (net (code "61") (name "unconnected-(IC6-PD5(T1)-Pad9)") (class "Default")
      (node (ref "IC6") (pin "9") (pinfunction "PD5(T1)_9") (pintype "bidirectional"))
    )
    (net (code "62") (name "unconnected-(IC6-PD6(AIN0)-Pad10)") (class "Default")
      (node (ref "IC6") (pin "10") (pinfunction "PD6(AIN0)_10") (pintype "bidirectional"))
    )
  )
)
